# IPIX_V2.net
KiCad netlist of a schematic drawn in EAGLE
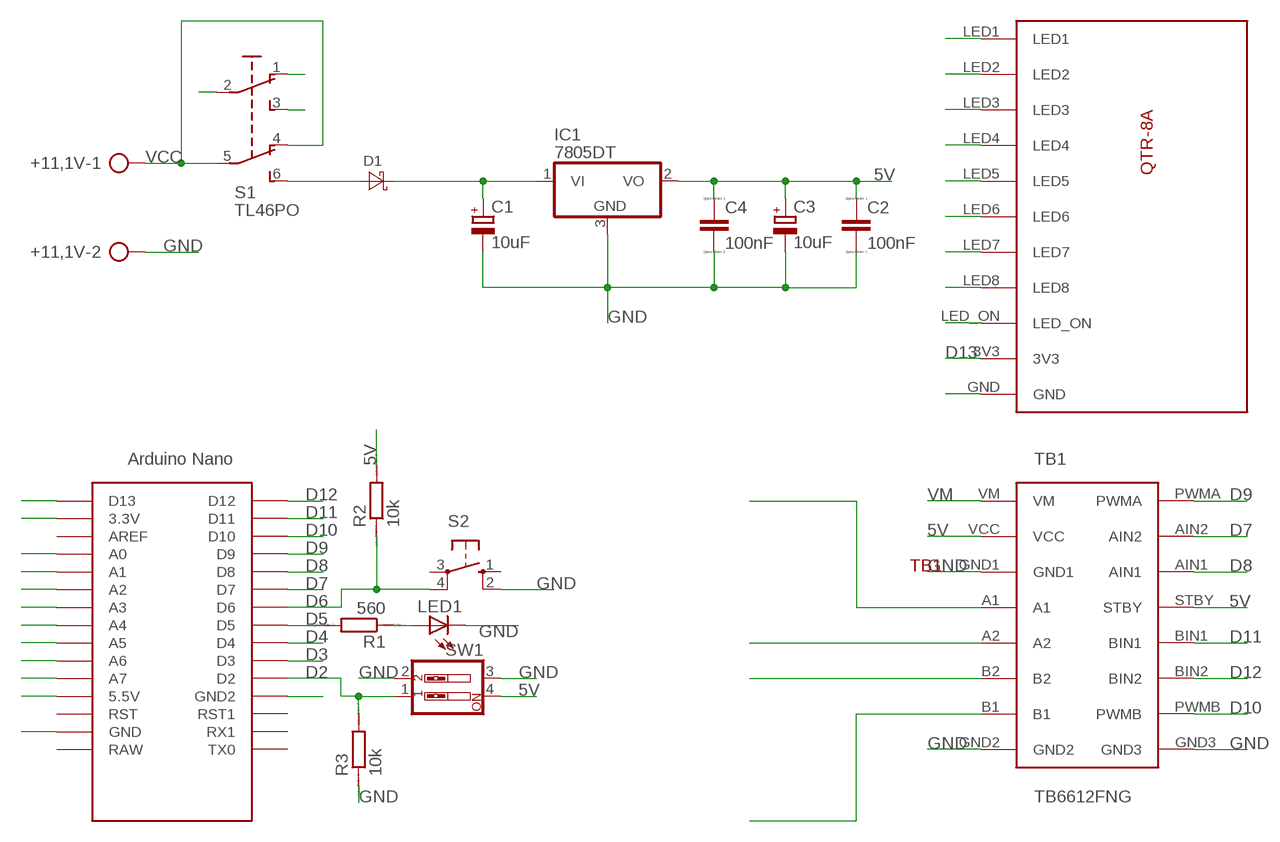
[diagram p0: schematic, sheet 1]

(export (version "E")
  (design (tool "Eeschema 10.0.6"))
  (components
    (comp (ref "+11,1V")
      (value "AK500/2-H")
      (footprint "eagle-import:AK500_2-H")
      (libsource (lib "eagle-import") (part "AK500/2-H"))
    )
    (comp (ref "C1")
      (value "10uF")
      (footprint "eagle-import:E2,5-6E")
      (libsource (lib "eagle-import") (part "CPOL-EUE2,5-6E"))
    )
    (comp (ref "C2")
      (value "100nF")
      (footprint "eagle-import:C0805")
      (libsource (lib "eagle-import") (part "C"))
    )
    (comp (ref "C3")
      (value "10uF")
      (footprint "eagle-import:E2,5-6E")
      (libsource (lib "eagle-import") (part "CPOL-EUE2,5-6E"))
    )
    (comp (ref "C4")
      (value "100nF")
      (footprint "eagle-import:C0805")
      (libsource (lib "eagle-import") (part "C"))
    )
    (comp (ref "D1")
      (value "DIODE-SCHOTTKY-DO201AD")
      (footprint "eagle-import:DO201AD")
      (libsource (lib "eagle-import") (part "DIODE-SCHOTTKY-DO201AD"))
    )
    (comp (ref "IC1")
      (value "7805DT")
      (footprint "eagle-import:TO252")
      (libsource (lib "eagle-import") (part "78DT05"))
    )
    (comp (ref "LED1")
      (value "LED3MM")
      (footprint "eagle-import:LED3MM")
      (libsource (lib "eagle-import") (part "LED3MM"))
    )
    (comp (ref "R1")
      (value "560")
      (footprint "eagle-import:0204_7")
      (libsource (lib "eagle-import") (part "R0204/7"))
    )
    (comp (ref "R2")
      (value "10k")
      (footprint "eagle-import:R0805")
      (libsource (lib "eagle-import") (part "R"))
    )
    (comp (ref "R3")
      (value "10k")
      (footprint "eagle-import:R0805")
      (libsource (lib "eagle-import") (part "R"))
    )
    (comp (ref "S1")
      (value "TL46PO")
      (footprint "eagle-import:TL4XPO")
      (libsource (lib "eagle-import") (part "TL46PO"))
    )
    (comp (ref "S2")
      (value "10-XX")
      (footprint "eagle-import:B3F-10XX")
      (fields (field (name "MPN") "B3F-1000"))
      (libsource (lib "eagle-import") (part "10-XX"))
    )
    (comp (ref "SW1")
      (value "SW_DIP-2")
      (footprint "eagle-import:EDG-02")
      (libsource (lib "eagle-import") (part "SW_DIP-2"))
    )
    (comp (ref "TB1")
      (value "TB6612FNG")
      (footprint "eagle-import:TB6612FNG")
      (libsource (lib "eagle-import") (part "TB6612FNG"))
    )
    (comp (ref "U$1")
      (value "NANO")
      (footprint "eagle-import:NANO")
      (libsource (lib "eagle-import") (part "NANO"))
    )
    (comp (ref "U$2")
      (value "QTR-8A")
      (footprint "eagle-import:QTR-8A")
      (fields (field (name "MF") "Pololu"))
      (libsource (lib "eagle-import") (part "QTR-8A"))
    )
  )
  (nets
    (net (code "1") (name "/5V") (class "Default")
      (node (ref "C2") (pin "1") (pinfunction "1_1") (pintype "passive"))
      (node (ref "C3") (pin "+") (pinfunction "+_+") (pintype "passive"))
      (node (ref "C4") (pin "1") (pinfunction "1_1") (pintype "passive"))
      (node (ref "IC1") (pin "2") (pinfunction "VO_2") (pintype "passive"))
      (node (ref "R2") (pin "2") (pinfunction "2_2") (pintype "passive"))
      (node (ref "SW1") (pin "4") (pinfunction "4_4") (pintype "passive"))
      (node (ref "TB1") (pin "STBY") (pinfunction "STBY_STBY") (pintype "bidirectional"))
      (node (ref "TB1") (pin "VCC") (pinfunction "VCC_VCC") (pintype "bidirectional"))
      (node (ref "U$1") (pin "5V") (pinfunction "5.5V_5V") (pintype "bidirectional"))
      (node (ref "U$2") (pin "LED8") (pinfunction "LED8_LED8") (pintype "bidirectional"))
    )
    (net (code "2") (name "/A0") (class "Default")
      (node (ref "U$1") (pin "A0") (pinfunction "A0_A0") (pintype "bidirectional"))
      (node (ref "U$2") (pin "LED_ON") (pinfunction "LED_ON_LED_ON") (pintype "bidirectional"))
    )
    (net (code "3") (name "/A1") (class "Default")
      (node (ref "U$1") (pin "A1") (pinfunction "A1_A1") (pintype "bidirectional"))
      (node (ref "U$2") (pin "LED1") (pinfunction "LED1_LED1") (pintype "bidirectional"))
    )
    (net (code "4") (name "/A2") (class "Default")
      (node (ref "U$1") (pin "A2") (pinfunction "A2_A2") (pintype "bidirectional"))
      (node (ref "U$2") (pin "LED2") (pinfunction "LED2_LED2") (pintype "bidirectional"))
    )
    (net (code "5") (name "/A3") (class "Default")
      (node (ref "U$1") (pin "A3") (pinfunction "A3_A3") (pintype "bidirectional"))
      (node (ref "U$2") (pin "LED3") (pinfunction "LED3_LED3") (pintype "bidirectional"))
    )
    (net (code "6") (name "/A4") (class "Default")
      (node (ref "U$1") (pin "A4") (pinfunction "A4_A4") (pintype "bidirectional"))
      (node (ref "U$2") (pin "LED4") (pinfunction "LED4_LED4") (pintype "bidirectional"))
    )
    (net (code "7") (name "/A5") (class "Default")
      (node (ref "U$1") (pin "A5") (pinfunction "A5_A5") (pintype "bidirectional"))
      (node (ref "U$2") (pin "LED5") (pinfunction "LED5_LED5") (pintype "bidirectional"))
    )
    (net (code "8") (name "/A6") (class "Default")
      (node (ref "U$1") (pin "A6") (pinfunction "A6_A6") (pintype "bidirectional"))
      (node (ref "U$2") (pin "LED6") (pinfunction "LED6_LED6") (pintype "bidirectional"))
    )
    (net (code "9") (name "/A7") (class "Default")
      (node (ref "U$1") (pin "A7") (pinfunction "A7_A7") (pintype "bidirectional"))
      (node (ref "U$2") (pin "LED7") (pinfunction "LED7_LED7") (pintype "bidirectional"))
    )
    (net (code "10") (name "/D2") (class "Default")
      (node (ref "R3") (pin "2") (pinfunction "2_2") (pintype "passive"))
      (node (ref "SW1") (pin "1") (pinfunction "1_1") (pintype "passive"))
      (node (ref "U$1") (pin "D2") (pinfunction "D2_D2") (pintype "bidirectional"))
    )
    (net (code "11") (name "/D3") (class "Default")
      (node (ref "U$1") (pin "D3") (pinfunction "D3_D3") (pintype "bidirectional"))
    )
    (net (code "12") (name "/D4") (class "Default")
      (node (ref "U$1") (pin "D4") (pinfunction "D4_D4") (pintype "bidirectional"))
    )
    (net (code "13") (name "/D5") (class "Default")
      (node (ref "R1") (pin "2") (pinfunction "2_2") (pintype "passive"))
      (node (ref "U$1") (pin "D5") (pinfunction "D5_D5") (pintype "bidirectional"))
    )
    (net (code "14") (name "/D6") (class "Default")
      (node (ref "R2") (pin "1") (pinfunction "1_1") (pintype "passive"))
      (node (ref "S2") (pin "4") (pinfunction "P1_4") (pintype "passive"))
      (node (ref "U$1") (pin "D6") (pinfunction "D6_D6") (pintype "bidirectional"))
    )
    (net (code "15") (name "/D7") (class "Default")
      (node (ref "TB1") (pin "AIN2") (pinfunction "AIN2_AIN2") (pintype "bidirectional"))
      (node (ref "U$1") (pin "D7") (pinfunction "D7_D7") (pintype "bidirectional"))
    )
    (net (code "16") (name "/D8") (class "Default")
      (node (ref "TB1") (pin "AIN1") (pinfunction "AIN1_AIN1") (pintype "bidirectional"))
      (node (ref "U$1") (pin "D8") (pinfunction "D8_D8") (pintype "bidirectional"))
    )
    (net (code "17") (name "/D9") (class "Default")
      (node (ref "TB1") (pin "PWMA") (pinfunction "PWMA_PWMA") (pintype "bidirectional"))
      (node (ref "U$1") (pin "D9") (pinfunction "D9_D9") (pintype "bidirectional"))
    )
    (net (code "18") (name "/D10") (class "Default")
      (node (ref "TB1") (pin "PWMB") (pinfunction "PWMB_PWMB") (pintype "bidirectional"))
      (node (ref "U$1") (pin "D10") (pinfunction "D10_D10") (pintype "bidirectional"))
    )
    (net (code "19") (name "/D11") (class "Default")
      (node (ref "TB1") (pin "BIN1") (pinfunction "BIN1_BIN1") (pintype "bidirectional"))
      (node (ref "U$1") (pin "D11") (pinfunction "D11_D11") (pintype "bidirectional"))
    )
    (net (code "20") (name "/D12") (class "Default")
      (node (ref "TB1") (pin "BIN2") (pinfunction "BIN2_BIN2") (pintype "bidirectional"))
      (node (ref "U$1") (pin "D12") (pinfunction "D12_D12") (pintype "bidirectional"))
    )
    (net (code "21") (name "/D13") (class "Default")
      (node (ref "U$1") (pin "D13") (pinfunction "D13_D13") (pintype "bidirectional"))
      (node (ref "U$2") (pin "3V3") (pinfunction "3V3_3V3") (pintype "bidirectional"))
    )
    (net (code "22") (name "/GND") (class "Default")
      (node (ref "+11,1V") (pin "2") (pinfunction "KL_2") (pintype "passive"))
      (node (ref "C1") (pin "-") (pinfunction "-_-") (pintype "passive"))
      (node (ref "C2") (pin "2") (pinfunction "2_2") (pintype "passive"))
      (node (ref "C3") (pin "-") (pinfunction "-_-") (pintype "passive"))
      (node (ref "C4") (pin "2") (pinfunction "2_2") (pintype "passive"))
      (node (ref "IC1") (pin "3") (pinfunction "GND_3") (pintype "passive"))
      (node (ref "LED1") (pin "K") (pinfunction "C_K") (pintype "passive"))
      (node (ref "R3") (pin "1") (pinfunction "1_1") (pintype "passive"))
      (node (ref "S1") (pin "1") (pinfunction "O_1") (pintype "passive"))
      (node (ref "S1") (pin "2") (pinfunction "P_2") (pintype "passive"))
      (node (ref "S1") (pin "3") (pinfunction "S_3") (pintype "passive"))
      (node (ref "S2") (pin "2") (pinfunction "S1_2") (pintype "passive"))
      (node (ref "SW1") (pin "2") (pinfunction "2_2") (pintype "passive"))
      (node (ref "SW1") (pin "3") (pinfunction "3_3") (pintype "passive"))
      (node (ref "TB1") (pin "GND1") (pinfunction "GND1_GND1") (pintype "bidirectional"))
      (node (ref "TB1") (pin "GND2") (pinfunction "GND2_GND2") (pintype "bidirectional"))
      (node (ref "TB1") (pin "GND3") (pinfunction "GND3_GND3") (pintype "bidirectional"))
      (node (ref "U$1") (pin "GND") (pinfunction "GND_GND") (pintype "bidirectional"))
      (node (ref "U$1") (pin "GND1") (pinfunction "GND2_GND1") (pintype "bidirectional"))
      (node (ref "U$2") (pin "GND") (pinfunction "GND_GND") (pintype "bidirectional"))
    )
    (net (code "23") (name "/VCC") (class "Default")
      (node (ref "+11,1V") (pin "1") (pinfunction "KL_1") (pintype "passive"))
      (node (ref "S1") (pin "4") (pinfunction "O1_4") (pintype "passive"))
      (node (ref "S1") (pin "5") (pinfunction "P1_5") (pintype "passive"))
    )
    (net (code "24") (name "/VM") (class "Default")
      (node (ref "C1") (pin "+") (pinfunction "+_+") (pintype "passive"))
      (node (ref "D1") (pin "C") (pinfunction "C_C") (pintype "passive"))
      (node (ref "IC1") (pin "1") (pinfunction "VI_1") (pintype "input"))
      (node (ref "TB1") (pin "VM") (pinfunction "VM_VM") (pintype "bidirectional"))
    )
    (net (code "25") (name "Net-(LED1-PadA)") (class "Default")
      (node (ref "LED1") (pin "A") (pinfunction "A_A") (pintype "passive"))
      (node (ref "R1") (pin "1") (pinfunction "1_1") (pintype "passive"))
    )
    (net (code "26") (name "Net-(S1-S1)") (class "Default")
      (node (ref "D1") (pin "A") (pinfunction "A_A") (pintype "passive"))
      (node (ref "S1") (pin "6") (pinfunction "S1_6") (pintype "passive"))
    )
    (net (code "27") (name "unconnected-(S2-P-Pad3)") (class "Default")
      (node (ref "S2") (pin "3") (pinfunction "P_3") (pintype "passive"))
    )
    (net (code "28") (name "unconnected-(S2-S-Pad1)") (class "Default")
      (node (ref "S2") (pin "1") (pinfunction "S_1") (pintype "passive"))
    )
    (net (code "29") (name "unconnected-(TB1-PadA1)") (class "Default")
      (node (ref "TB1") (pin "A1") (pinfunction "A1_A1") (pintype "bidirectional"))
    )
    (net (code "30") (name "unconnected-(TB1-PadA2)") (class "Default")
      (node (ref "TB1") (pin "A2") (pinfunction "A2_A2") (pintype "bidirectional"))
    )
    (net (code "31") (name "unconnected-(TB1-PadB1)") (class "Default")
      (node (ref "TB1") (pin "B1") (pinfunction "B1_B1") (pintype "bidirectional"))
    )
    (net (code "32") (name "unconnected-(TB1-PadB2)") (class "Default")
      (node (ref "TB1") (pin "B2") (pinfunction "B2_B2") (pintype "bidirectional"))
    )
    (net (code "33") (name "unconnected-(U$1-Pad3.3V)") (class "Default")
      (node (ref "U$1") (pin "3.3V") (pinfunction "3.3V_3.3V") (pintype "bidirectional"))
    )
    (net (code "34") (name "unconnected-(U$1-PadAREF)") (class "Default")
      (node (ref "U$1") (pin "AREF") (pinfunction "AREF_AREF") (pintype "bidirectional"))
    )
    (net (code "35") (name "unconnected-(U$1-PadICSP1)") (class "Default")
      (node (ref "U$1") (pin "ICSP1") (pinfunction "ICSP1_ICSP1") (pintype "bidirectional"))
    )
    (net (code "36") (name "unconnected-(U$1-PadICSP2)") (class "Default")
      (node (ref "U$1") (pin "ICSP2") (pinfunction "ICSP2_ICSP2") (pintype "bidirectional"))
    )
    (net (code "37") (name "unconnected-(U$1-PadICSP3)") (class "Default")
      (node (ref "U$1") (pin "ICSP3") (pinfunction "ICSP3_ICSP3") (pintype "bidirectional"))
    )
    (net (code "38") (name "unconnected-(U$1-PadICSP4)") (class "Default")
      (node (ref "U$1") (pin "ICSP4") (pinfunction "ICSP4_ICSP4") (pintype "bidirectional"))
    )
    (net (code "39") (name "unconnected-(U$1-PadICSP5)") (class "Default")
      (node (ref "U$1") (pin "ICSP5") (pinfunction "ICSP5_ICSP5") (pintype "bidirectional"))
    )
    (net (code "40") (name "unconnected-(U$1-PadICSP6)") (class "Default")
      (node (ref "U$1") (pin "ICSP6") (pinfunction "ICSP6_ICSP6") (pintype "bidirectional"))
    )
    (net (code "41") (name "unconnected-(U$1-PadRAW)") (class "Default")
      (node (ref "U$1") (pin "RAW") (pinfunction "RAW_RAW") (pintype "bidirectional"))
    )
    (net (code "42") (name "unconnected-(U$1-PadRST)") (class "Default")
      (node (ref "U$1") (pin "RST") (pinfunction "RST_RST") (pintype "bidirectional"))
    )
    (net (code "43") (name "unconnected-(U$1-PadRST1)") (class "Default")
      (node (ref "U$1") (pin "RST1") (pinfunction "RST1_RST1") (pintype "bidirectional"))
    )
    (net (code "44") (name "unconnected-(U$1-PadRX1)") (class "Default")
      (node (ref "U$1") (pin "RX1") (pinfunction "RX1_RX1") (pintype "bidirectional"))
    )
    (net (code "45") (name "unconnected-(U$1-PadTX0)") (class "Default")
      (node (ref "U$1") (pin "TX0") (pinfunction "TX0_TX0") (pintype "bidirectional"))
    )
  )
)
